# encoder.net
KiCad netlist of a schematic drawn in EAGLE
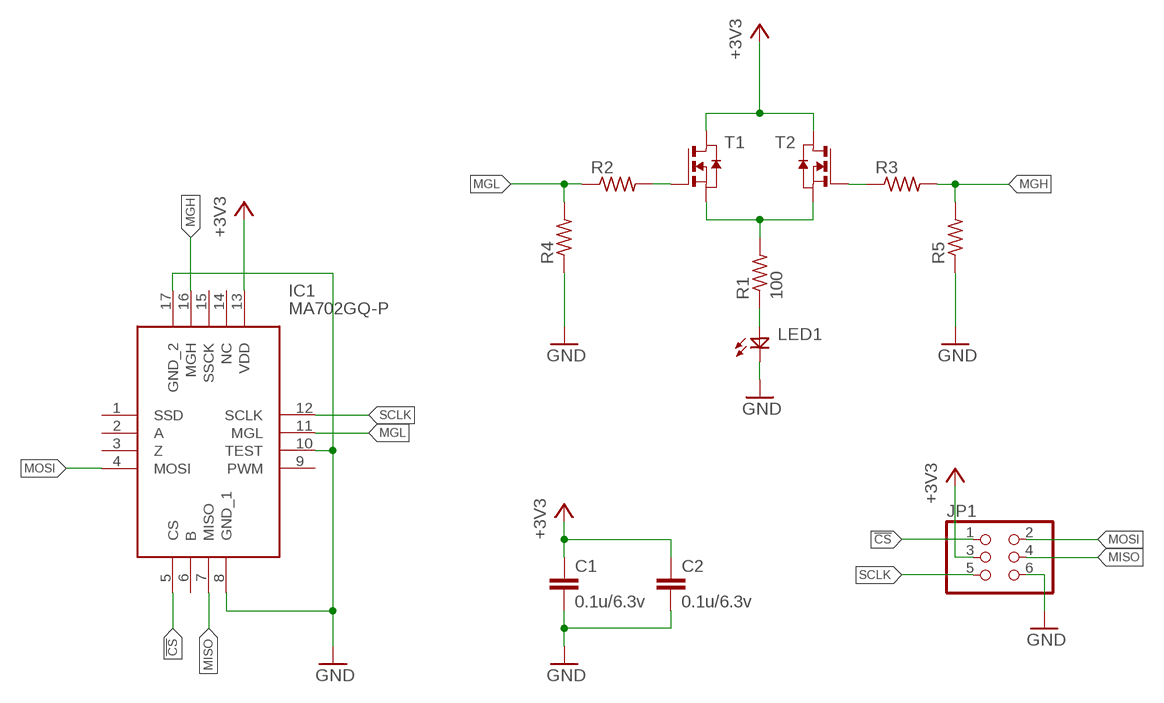
[diagram p0: schematic, sheet 1]

(export (version "E")
  (design (tool "Eeschema 10.0.6"))
  (components
    (comp (ref "C1")
      (value "0.1u/6.3v")
      (footprint "eagle-import:C0603")
      (libsource (lib "eagle-import") (part "C-EUC0603"))
    )
    (comp (ref "C2")
      (value "0.1u/6.3v")
      (footprint "eagle-import:C0603")
      (libsource (lib "eagle-import") (part "C-EUC0603"))
    )
    (comp (ref "IC1")
      (value "MA702GQ-P")
      (footprint "eagle-import:QFN50P300X300X100-17N")
      (libsource (lib "eagle-import") (part "MA702GQ-P"))
    )
    (comp (ref "JP1")
      (value "PINHD-2X3/90")
      (footprint "eagle-import:2X03_90")
      (libsource (lib "eagle-import") (part "PINHD-2X3/90"))
    )
    (comp (ref "LED1")
      (value "LED1608")
      (footprint "eagle-import:LED1608")
      (libsource (lib "eagle-import") (part "LED1608"))
    )
    (comp (ref "R1")
      (value "100")
      (footprint "eagle-import:R0603")
      (libsource (lib "eagle-import") (part "R-US_R0603"))
    )
    (comp (ref "R2")
      (value "R-US_R0603")
      (footprint "eagle-import:R0603")
      (libsource (lib "eagle-import") (part "R-US_R0603"))
    )
    (comp (ref "R3")
      (value "R-US_R0603")
      (footprint "eagle-import:R0603")
      (libsource (lib "eagle-import") (part "R-US_R0603"))
    )
    (comp (ref "R4")
      (value "R-US_R0603")
      (footprint "eagle-import:R0603")
      (libsource (lib "eagle-import") (part "R-US_R0603"))
    )
    (comp (ref "R5")
      (value "R-US_R0603")
      (footprint "eagle-import:R0603")
      (libsource (lib "eagle-import") (part "R-US_R0603"))
    )
    (comp (ref "T1")
      (value "NMOSSOT23")
      (footprint "eagle-import:SOT-23")
      (libsource (lib "eagle-import") (part "NMOSSOT23"))
    )
    (comp (ref "T2")
      (value "NMOSSOT23")
      (footprint "eagle-import:SOT-23")
      (libsource (lib "eagle-import") (part "NMOSSOT23"))
    )
  )
  (nets
    (net (code "1") (name "+3V3") (class "Default")
      (node (ref "C1") (pin "1") (pinfunction "1_1") (pintype "passive"))
      (node (ref "C2") (pin "1") (pinfunction "1_1") (pintype "passive"))
      (node (ref "IC1") (pin "13") (pinfunction "VDD_13") (pintype "bidirectional"))
      (node (ref "JP1") (pin "3") (pinfunction "3_3") (pintype "passive"))
      (node (ref "T1") (pin "1") (pinfunction "D_1") (pintype "passive"))
      (node (ref "T2") (pin "1") (pinfunction "D_1") (pintype "passive"))
    )
    (net (code "2") (name "/~{CS}") (class "Default")
      (node (ref "IC1") (pin "5") (pinfunction "CS_5") (pintype "bidirectional"))
      (node (ref "JP1") (pin "1") (pinfunction "1_1") (pintype "passive"))
    )
    (net (code "3") (name "GND") (class "Default")
      (node (ref "C1") (pin "2") (pinfunction "2_2") (pintype "passive"))
      (node (ref "C2") (pin "2") (pinfunction "2_2") (pintype "passive"))
      (node (ref "IC1") (pin "10") (pinfunction "TEST_10") (pintype "bidirectional"))
      (node (ref "IC1") (pin "17") (pinfunction "GND_2_17") (pintype "bidirectional"))
      (node (ref "IC1") (pin "8") (pinfunction "GND_1_8") (pintype "bidirectional"))
      (node (ref "JP1") (pin "6") (pinfunction "6_6") (pintype "passive"))
      (node (ref "LED1") (pin "K") (pinfunction "K_K") (pintype "passive"))
      (node (ref "R4") (pin "1") (pinfunction "1_1") (pintype "passive"))
      (node (ref "R5") (pin "1") (pinfunction "1_1") (pintype "passive"))
    )
    (net (code "4") (name "MGH") (class "Default")
      (node (ref "IC1") (pin "16") (pinfunction "MGH_16") (pintype "bidirectional"))
      (node (ref "R3") (pin "2") (pinfunction "2_2") (pintype "passive"))
      (node (ref "R5") (pin "2") (pinfunction "2_2") (pintype "passive"))
    )
    (net (code "5") (name "MGL") (class "Default")
      (node (ref "IC1") (pin "11") (pinfunction "MGL_11") (pintype "bidirectional"))
      (node (ref "R2") (pin "1") (pinfunction "1_1") (pintype "passive"))
      (node (ref "R4") (pin "2") (pinfunction "2_2") (pintype "passive"))
    )
    (net (code "6") (name "MISO") (class "Default")
      (node (ref "IC1") (pin "7") (pinfunction "MISO_7") (pintype "bidirectional"))
      (node (ref "JP1") (pin "4") (pinfunction "4_4") (pintype "passive"))
    )
    (net (code "7") (name "MOSI") (class "Default")
      (node (ref "IC1") (pin "4") (pinfunction "MOSI_4") (pintype "bidirectional"))
      (node (ref "JP1") (pin "2") (pinfunction "2_2") (pintype "passive"))
    )
    (net (code "8") (name "Net-(LED1-PadA)") (class "Default")
      (node (ref "LED1") (pin "A") (pinfunction "A_A") (pintype "passive"))
      (node (ref "R1") (pin "1") (pinfunction "1_1") (pintype "passive"))
    )
    (net (code "9") (name "Net-(T1-G)") (class "Default")
      (node (ref "R2") (pin "2") (pinfunction "2_2") (pintype "passive"))
      (node (ref "T1") (pin "3") (pinfunction "G_3") (pintype "passive"))
    )
    (net (code "10") (name "Net-(T1-S)") (class "Default")
      (node (ref "R1") (pin "2") (pinfunction "2_2") (pintype "passive"))
      (node (ref "T1") (pin "2") (pinfunction "S_2") (pintype "passive"))
      (node (ref "T2") (pin "2") (pinfunction "S_2") (pintype "passive"))
    )
    (net (code "11") (name "Net-(T2-G)") (class "Default")
      (node (ref "R3") (pin "1") (pinfunction "1_1") (pintype "passive"))
      (node (ref "T2") (pin "3") (pinfunction "G_3") (pintype "passive"))
    )
    (net (code "12") (name "SCLK") (class "Default")
      (node (ref "IC1") (pin "12") (pinfunction "SCLK_12") (pintype "bidirectional"))
      (node (ref "JP1") (pin "5") (pinfunction "5_5") (pintype "passive"))
    )
    (net (code "13") (name "unconnected-(IC1-A-Pad2)") (class "Default")
      (node (ref "IC1") (pin "2") (pinfunction "A_2") (pintype "bidirectional"))
    )
    (net (code "14") (name "unconnected-(IC1-B-Pad6)") (class "Default")
      (node (ref "IC1") (pin "6") (pinfunction "B_6") (pintype "bidirectional"))
    )
    (net (code "15") (name "unconnected-(IC1-NC-Pad14)") (class "Default")
      (node (ref "IC1") (pin "14") (pinfunction "NC_14") (pintype "no_connect"))
    )
    (net (code "16") (name "unconnected-(IC1-PWM-Pad9)") (class "Default")
      (node (ref "IC1") (pin "9") (pinfunction "PWM_9") (pintype "bidirectional"))
    )
    (net (code "17") (name "unconnected-(IC1-SSCK-Pad15)") (class "Default")
      (node (ref "IC1") (pin "15") (pinfunction "SSCK_15") (pintype "bidirectional"))
    )
    (net (code "18") (name "unconnected-(IC1-SSD-Pad1)") (class "Default")
      (node (ref "IC1") (pin "1") (pinfunction "SSD_1") (pintype "bidirectional"))
    )
    (net (code "19") (name "unconnected-(IC1-Z-Pad3)") (class "Default")
      (node (ref "IC1") (pin "3") (pinfunction "Z_3") (pintype "bidirectional"))
    )
  )
)
